# mainBoardV1.net
KiCad netlist of a schematic drawn in EAGLE
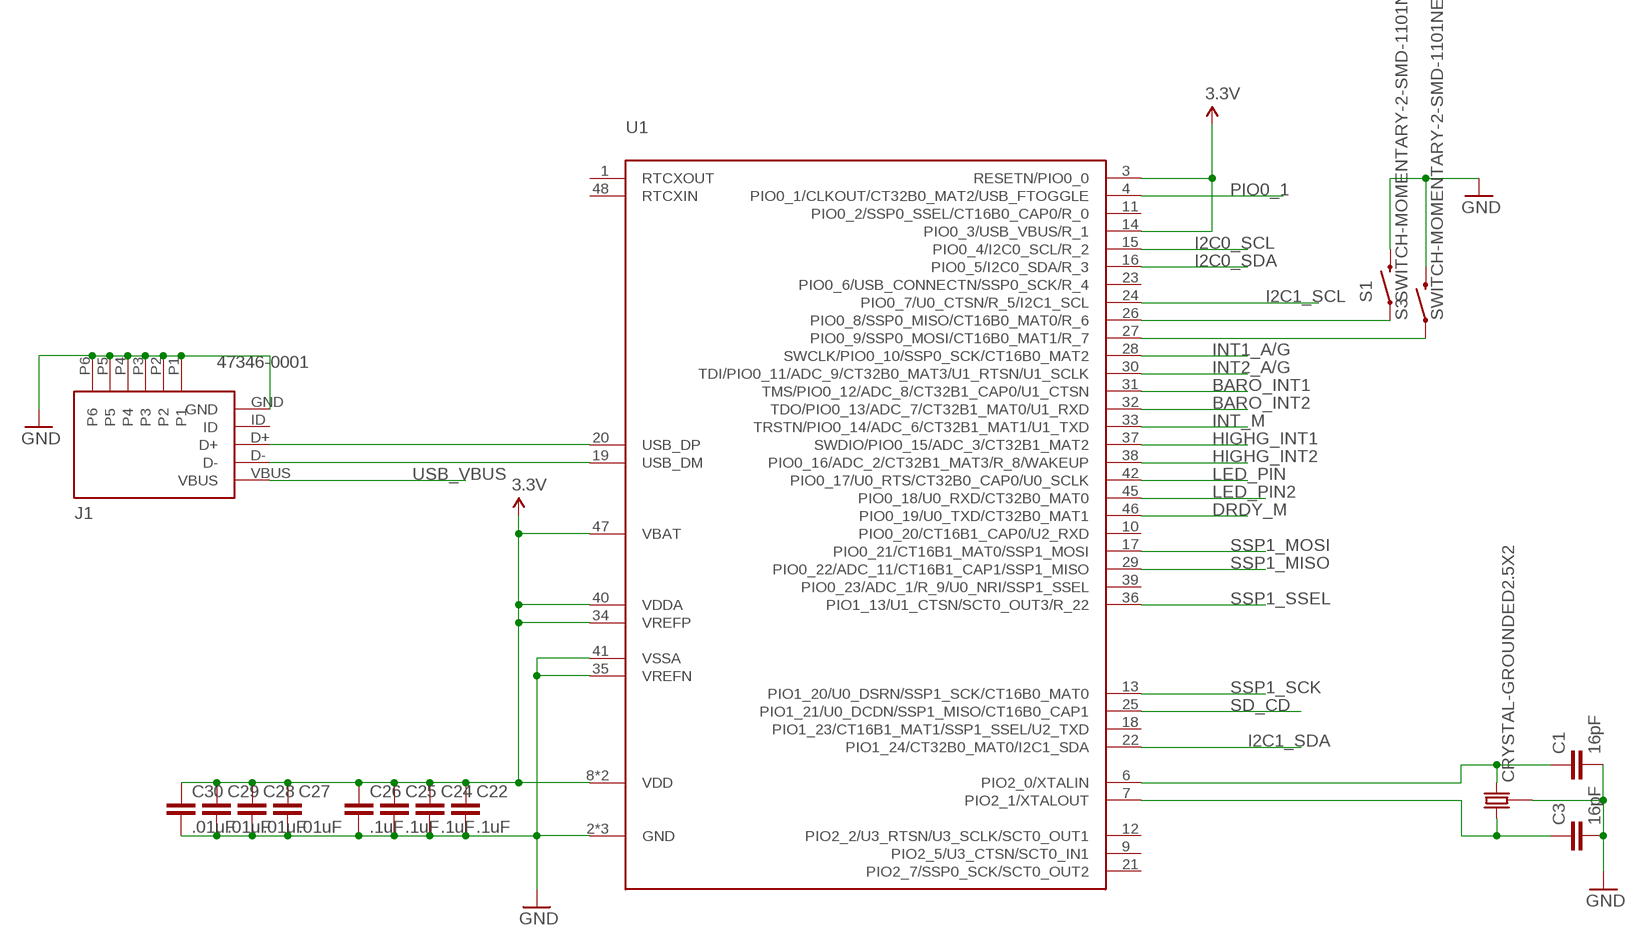
[diagram p0: schematic, sheet 1]
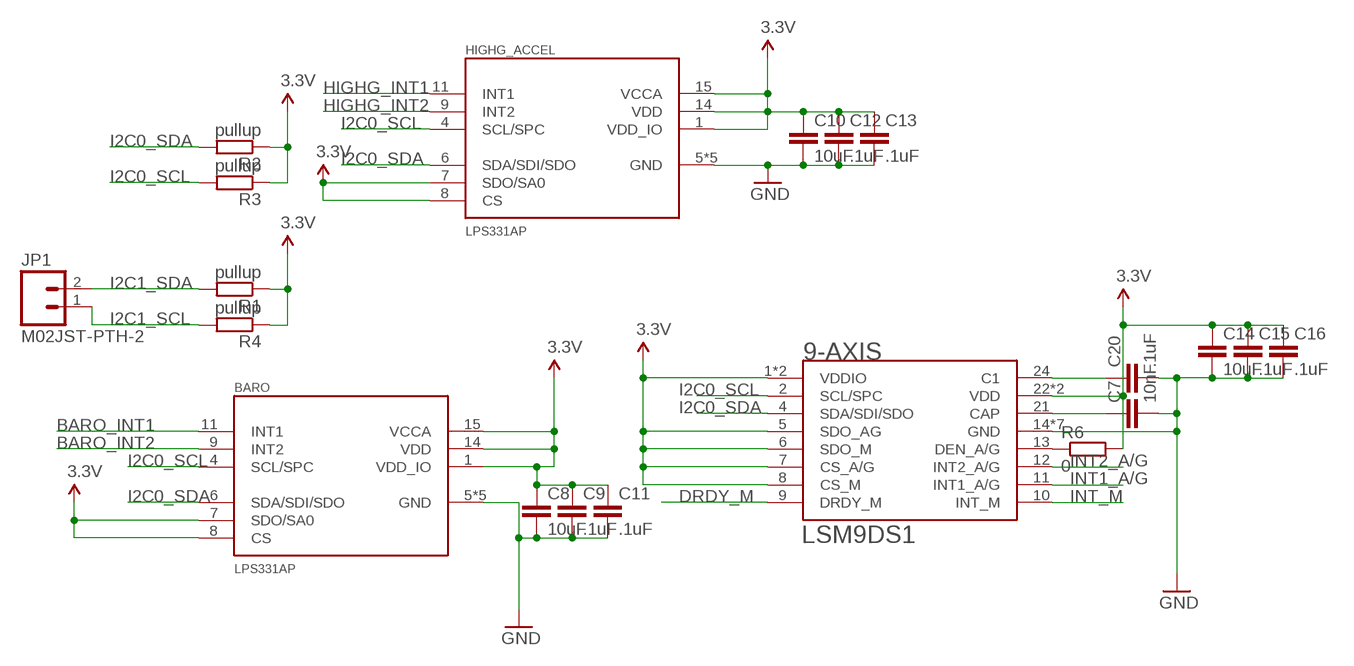
[diagram p1: schematic, sheet 2]
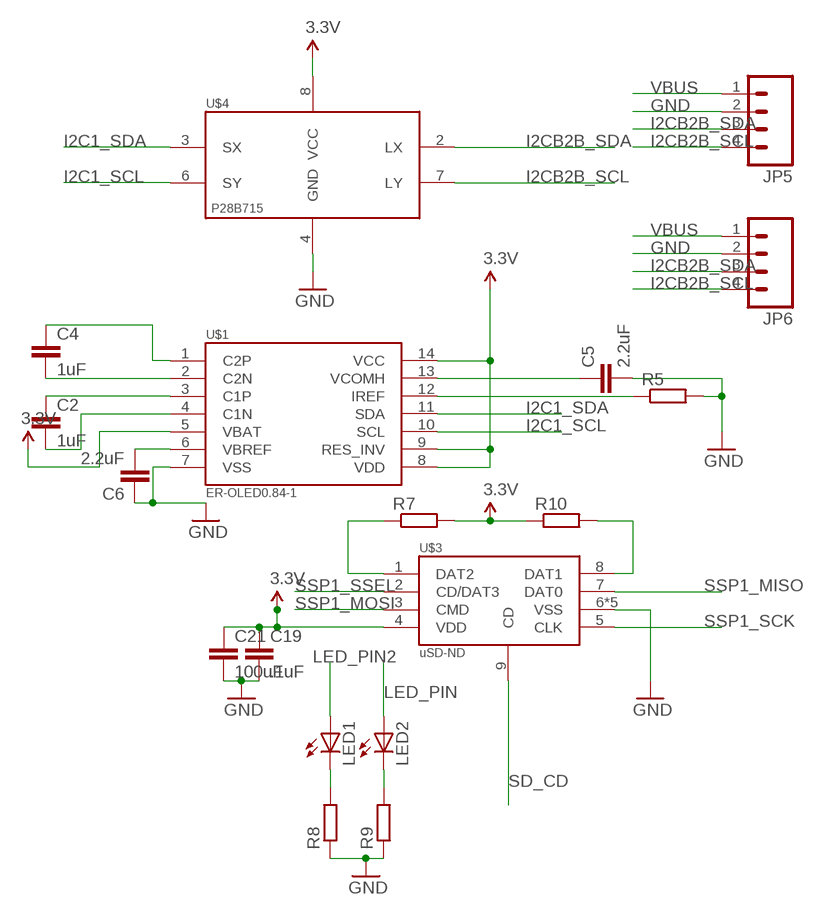
[diagram p2: schematic, sheet 3]
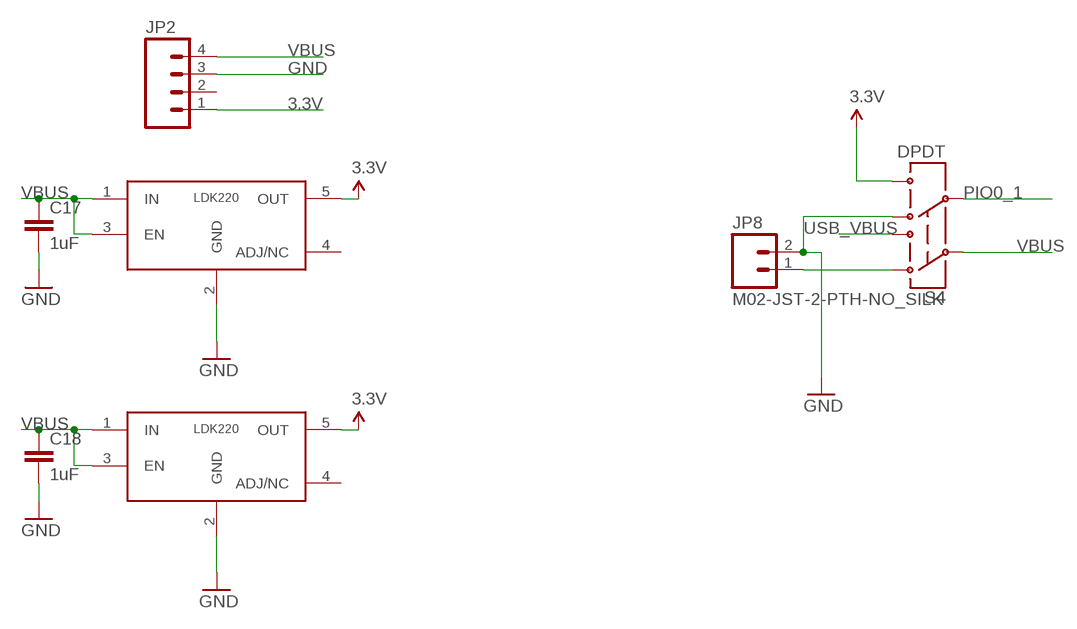
[diagram p3: schematic, sheet 4]

(export (version "E")
  (design (tool "Eeschema 10.0.6"))
  (components
    (comp (ref "C2")
      (value "1uF")
      (footprint "eagle-import:C0402")
      (fields (field (name "MPN") "MC0402X105M6R3CT"))
      (libsource (lib "eagle-import") (part "C0402"))
    )
    (comp (ref "C4")
      (value "1uF")
      (footprint "eagle-import:C0402")
      (fields (field (name "MPN") "MC0402X105M6R3CT"))
      (libsource (lib "eagle-import") (part "C0402"))
    )
    (comp (ref "C5")
      (value "2.2uF")
      (footprint "eagle-import:C0402")
      (fields (field (name "MPN") "C1005X6S0G225M050BC"))
      (libsource (lib "eagle-import") (part "C0402"))
    )
    (comp (ref "C6")
      (value "2.2uF")
      (footprint "eagle-import:C0402")
      (fields (field (name "MPN") "C1005X6S0G225M050BC"))
      (libsource (lib "eagle-import") (part "C0402"))
    )
    (comp (ref "C19")
      (value ".1uF")
      (footprint "eagle-import:C0402")
      (libsource (lib "eagle-import") (part "C0402"))
    )
    (comp (ref "C21")
      (value "100uF")
      (footprint "eagle-import:C1206")
      (libsource (lib "eagle-import") (part "CC1206"))
    )
    (comp (ref "JP5")
      (value "M04JST")
      (footprint "eagle-import:1X04-1.5MM_JST")
      (libsource (lib "eagle-import") (part "M04JST"))
    )
    (comp (ref "JP6")
      (value "M04JST")
      (footprint "eagle-import:1X04-1.5MM_JST")
      (libsource (lib "eagle-import") (part "M04JST"))
    )
    (comp (ref "LED1")
      (value "LEDCHIPLED_0603")
      (footprint "eagle-import:CHIPLED_0603")
      (libsource (lib "eagle-import") (part "LEDCHIPLED_0603"))
    )
    (comp (ref "LED2")
      (value "LEDCHIPLED_0603")
      (footprint "eagle-import:CHIPLED_0603")
      (libsource (lib "eagle-import") (part "LEDCHIPLED_0603"))
    )
    (comp (ref "R5")
      (value "R0402")
      (footprint "eagle-import:R0402")
      (libsource (lib "eagle-import") (part "R0402"))
    )
    (comp (ref "R7")
      (value "R0402")
      (footprint "eagle-import:R0402")
      (libsource (lib "eagle-import") (part "R0402"))
    )
    (comp (ref "R8")
      (value "R0402")
      (footprint "eagle-import:R0402")
      (libsource (lib "eagle-import") (part "R0402"))
    )
    (comp (ref "R9")
      (value "R0402")
      (footprint "eagle-import:R0402")
      (libsource (lib "eagle-import") (part "R0402"))
    )
    (comp (ref "R10")
      (value "R0402")
      (footprint "eagle-import:R0402")
      (libsource (lib "eagle-import") (part "R0402"))
    )
    (comp (ref "U$1")
      (value "ER-OLED0.84-1")
      (footprint "eagle-import:MOLEX_52892-1433")
      (libsource (lib "eagle-import") (part "ER-OLED0.84-1"))
    )
    (comp (ref "U$3")
      (value "MICROSD-CD")
      (footprint "eagle-import:MOLEX_SD-47352-101")
      (libsource (lib "eagle-import") (part "MICROSD-CD"))
    )
    (comp (ref "U$4")
      (value "P82B715")
      (footprint "eagle-import:SO8")
      (libsource (lib "eagle-import") (part "P82B715"))
    )
    (comp (ref "C1")
      (value "16pF")
      (footprint "eagle-import:C0402")
      (libsource (lib "eagle-import") (part "C0402"))
    )
    (comp (ref "C3")
      (value "16pF")
      (footprint "eagle-import:C0402")
      (libsource (lib "eagle-import") (part "C0402"))
    )
    (comp (ref "C22")
      (value ".1uF")
      (footprint "eagle-import:C0402")
      (libsource (lib "eagle-import") (part "C0402"))
    )
    (comp (ref "C24")
      (value ".1uF")
      (footprint "eagle-import:C0402")
      (libsource (lib "eagle-import") (part "C0402"))
    )
    (comp (ref "C25")
      (value ".1uF")
      (footprint "eagle-import:C0402")
      (libsource (lib "eagle-import") (part "C0402"))
    )
    (comp (ref "C26")
      (value ".1uF")
      (footprint "eagle-import:C0402")
      (libsource (lib "eagle-import") (part "C0402"))
    )
    (comp (ref "C27")
      (value ".01uF")
      (footprint "eagle-import:C0402")
      (libsource (lib "eagle-import") (part "C0402"))
    )
    (comp (ref "C28")
      (value ".01uF")
      (footprint "eagle-import:C0402")
      (libsource (lib "eagle-import") (part "C0402"))
    )
    (comp (ref "C29")
      (value ".01uF")
      (footprint "eagle-import:C0402")
      (libsource (lib "eagle-import") (part "C0402"))
    )
    (comp (ref "C30")
      (value ".01uF")
      (footprint "eagle-import:C0402")
      (libsource (lib "eagle-import") (part "C0402"))
    )
    (comp (ref "J1")
      (value "47346-0001")
      (footprint "eagle-import:MICRO_USB")
      (fields (field (name "PARTNO") "AS-ITM-00021"))
      (libsource (lib "eagle-import") (part "MICRO-USB"))
    )
    (comp (ref "S1")
      (value "SWITCH-MOMENTARY-2-SMD-1101NE")
      (footprint "eagle-import:TACTILE-SWITCH-1101NE")
      (libsource (lib "eagle-import") (part "SWITCH-MOMENTARY-2-SMD-1101NE"))
    )
    (comp (ref "S3")
      (value "SWITCH-MOMENTARY-2-SMD-1101NE")
      (footprint "eagle-import:TACTILE-SWITCH-1101NE")
      (libsource (lib "eagle-import") (part "SWITCH-MOMENTARY-2-SMD-1101NE"))
    )
    (comp (ref "U$5")
      (value "CRYSTAL-GROUNDED2.5X2")
      (footprint "eagle-import:CRYSTAL-SMD-2.5X2")
      (libsource (lib "eagle-import") (part "CRYSTAL-GROUNDED2.5X2"))
    )
    (comp (ref "U1")
      (value "LPC11U68JBD48")
      (footprint "eagle-import:LQFP48")
      (libsource (lib "eagle-import") (part "LPC11U68JBD48"))
    )
    (comp (ref "9-AXIS")
      (value "LSM9DS1")
      (footprint "eagle-import:LGA-24L-3.5X3X1")
      (libsource (lib "eagle-import") (part "LSM9DS1"))
    )
    (comp (ref "BARO")
      (value "LPS331AP")
      (footprint "eagle-import:LGA-16-3X3X1")
      (fields (field (name "MPN") "LPS331APTR"))
      (libsource (lib "eagle-import") (part "LPS331AP"))
    )
    (comp (ref "C7")
      (value "10nF")
      (footprint "eagle-import:C0402")
      (fields (field (name "MPN") "S103M47Z5UN63L0R"))
      (libsource (lib "eagle-import") (part "C0402"))
    )
    (comp (ref "C8")
      (value "10uF")
      (footprint "eagle-import:C0402")
      (libsource (lib "eagle-import") (part "C0402"))
    )
    (comp (ref "C9")
      (value ".1uF")
      (footprint "eagle-import:C0402")
      (libsource (lib "eagle-import") (part "C0402"))
    )
    (comp (ref "C10")
      (value "10uF")
      (footprint "eagle-import:C0402")
      (libsource (lib "eagle-import") (part "C0402"))
    )
    (comp (ref "C11")
      (value ".1uF")
      (footprint "eagle-import:C0402")
      (libsource (lib "eagle-import") (part "C0402"))
    )
    (comp (ref "C12")
      (value ".1uF")
      (footprint "eagle-import:C0402")
      (libsource (lib "eagle-import") (part "C0402"))
    )
    (comp (ref "C13")
      (value ".1uF")
      (footprint "eagle-import:C0402")
      (libsource (lib "eagle-import") (part "C0402"))
    )
    (comp (ref "C14")
      (value "10uF")
      (footprint "eagle-import:C0402")
      (libsource (lib "eagle-import") (part "C0402"))
    )
    (comp (ref "C15")
      (value ".1uF")
      (footprint "eagle-import:C0402")
      (libsource (lib "eagle-import") (part "C0402"))
    )
    (comp (ref "C16")
      (value ".1uF")
      (footprint "eagle-import:C0402")
      (libsource (lib "eagle-import") (part "C0402"))
    )
    (comp (ref "C20")
      (value ".1uF")
      (footprint "eagle-import:C0402")
      (fields (field (name "MPN") "S103M47Z5UN63L0R"))
      (libsource (lib "eagle-import") (part "C0402"))
    )
    (comp (ref "HIGHG_ACCEL")
      (value "LPS331AP")
      (footprint "eagle-import:LGA-16-3X3X1")
      (fields (field (name "MPN") "LPS331APTR"))
      (libsource (lib "eagle-import") (part "LPS331AP"))
    )
    (comp (ref "JP1")
      (value "M02JST-PTH-2")
      (footprint "eagle-import:JST-2-PTH")
      (libsource (lib "eagle-import") (part "M02JST-PTH-2"))
    )
    (comp (ref "R1")
      (value "pullup")
      (footprint "eagle-import:R0805")
      (libsource (lib "eagle-import") (part "R0805"))
    )
    (comp (ref "R2")
      (value "pullup")
      (footprint "eagle-import:R0402")
      (libsource (lib "eagle-import") (part "R0402"))
    )
    (comp (ref "R3")
      (value "pullup")
      (footprint "eagle-import:R0402")
      (libsource (lib "eagle-import") (part "R0402"))
    )
    (comp (ref "R4")
      (value "pullup")
      (footprint "eagle-import:R0805")
      (libsource (lib "eagle-import") (part "R0805"))
    )
    (comp (ref "R6")
      (value "0")
      (footprint "eagle-import:R0402")
      (libsource (lib "eagle-import") (part "R0402"))
    )
    (comp (ref "C17")
      (value "1uF")
      (footprint "eagle-import:C0402")
      (libsource (lib "eagle-import") (part "C0402"))
    )
    (comp (ref "C18")
      (value "1uF")
      (footprint "eagle-import:C0402")
      (libsource (lib "eagle-import") (part "C0402"))
    )
    (comp (ref "JP2")
      (value "M04JST")
      (footprint "eagle-import:1X04-1.5MM_JST")
      (libsource (lib "eagle-import") (part "M04JST"))
    )
    (comp (ref "JP8")
      (value "M02-JST-2-PTH-NO_SILK")
      (footprint "eagle-import:JST-2-PTH-NS")
      (libsource (lib "eagle-import") (part "M02-JST-2-PTH-NO_SILK"))
    )
    (comp (ref "S4")
      (value "DPDT")
      (footprint "eagle-import:AYZ0202")
      (libsource (lib "eagle-import") (part "SWITCH-DPDTAYZ0202"))
    )
    (comp (ref "U$2")
      (value "LDK220M33R")
      (footprint "eagle-import:SOT23-5")
      (libsource (lib "eagle-import") (part "LDK220M33R"))
    )
    (comp (ref "U$6")
      (value "LDK220M33R")
      (footprint "eagle-import:SOT23-5")
      (libsource (lib "eagle-import") (part "LDK220M33R"))
    )
  )
  (nets
    (net (code "1") (name "3.3V") (class "Default")
      (node (ref "9-AXIS") (pin "1") (pinfunction "VDDIO_1") (pintype "bidirectional"))
      (node (ref "9-AXIS") (pin "22") (pinfunction "VDD_22") (pintype "bidirectional"))
      (node (ref "9-AXIS") (pin "23") (pinfunction "VDD_23") (pintype "bidirectional"))
      (node (ref "9-AXIS") (pin "3") (pinfunction "VDDIO_3") (pintype "bidirectional"))
      (node (ref "9-AXIS") (pin "5") (pinfunction "SDO_AG_5") (pintype "bidirectional"))
      (node (ref "9-AXIS") (pin "6") (pinfunction "SDO_M_6") (pintype "bidirectional"))
      (node (ref "9-AXIS") (pin "7") (pinfunction "CS_A/G_7") (pintype "bidirectional"))
      (node (ref "9-AXIS") (pin "8") (pinfunction "CS_M_8") (pintype "bidirectional"))
      (node (ref "BARO") (pin "1") (pinfunction "VDD_IO_1") (pintype "bidirectional"))
      (node (ref "BARO") (pin "14") (pinfunction "VDD_14") (pintype "bidirectional"))
      (node (ref "BARO") (pin "15") (pinfunction "VCCA_15") (pintype "bidirectional"))
      (node (ref "BARO") (pin "7") (pinfunction "SDO/SA0_7") (pintype "bidirectional"))
      (node (ref "BARO") (pin "8") (pinfunction "CS_8") (pintype "bidirectional"))
      (node (ref "C10") (pin "1") (pinfunction "1_1") (pintype "passive"))
      (node (ref "C11") (pin "1") (pinfunction "1_1") (pintype "passive"))
      (node (ref "C12") (pin "1") (pinfunction "1_1") (pintype "passive"))
      (node (ref "C13") (pin "1") (pinfunction "1_1") (pintype "passive"))
      (node (ref "C14") (pin "1") (pinfunction "1_1") (pintype "passive"))
      (node (ref "C15") (pin "1") (pinfunction "1_1") (pintype "passive"))
      (node (ref "C16") (pin "1") (pinfunction "1_1") (pintype "passive"))
      (node (ref "C19") (pin "1") (pinfunction "1_1") (pintype "passive"))
      (node (ref "C21") (pin "1") (pinfunction "1_1") (pintype "passive"))
      (node (ref "C22") (pin "1") (pinfunction "1_1") (pintype "passive"))
      (node (ref "C24") (pin "1") (pinfunction "1_1") (pintype "passive"))
      (node (ref "C25") (pin "1") (pinfunction "1_1") (pintype "passive"))
      (node (ref "C26") (pin "1") (pinfunction "1_1") (pintype "passive"))
      (node (ref "C27") (pin "1") (pinfunction "1_1") (pintype "passive"))
      (node (ref "C28") (pin "1") (pinfunction "1_1") (pintype "passive"))
      (node (ref "C29") (pin "1") (pinfunction "1_1") (pintype "passive"))
      (node (ref "C30") (pin "1") (pinfunction "1_1") (pintype "passive"))
      (node (ref "C8") (pin "1") (pinfunction "1_1") (pintype "passive"))
      (node (ref "C9") (pin "1") (pinfunction "1_1") (pintype "passive"))
      (node (ref "HIGHG_ACCEL") (pin "1") (pinfunction "VDD_IO_1") (pintype "bidirectional"))
      (node (ref "HIGHG_ACCEL") (pin "14") (pinfunction "VDD_14") (pintype "bidirectional"))
      (node (ref "HIGHG_ACCEL") (pin "15") (pinfunction "VCCA_15") (pintype "bidirectional"))
      (node (ref "HIGHG_ACCEL") (pin "7") (pinfunction "SDO/SA0_7") (pintype "bidirectional"))
      (node (ref "HIGHG_ACCEL") (pin "8") (pinfunction "CS_8") (pintype "bidirectional"))
      (node (ref "JP2") (pin "1") (pinfunction "1_1") (pintype "passive"))
      (node (ref "R1") (pin "1") (pinfunction "1_1") (pintype "passive"))
      (node (ref "R10") (pin "1") (pinfunction "1_1") (pintype "passive"))
      (node (ref "R2") (pin "1") (pinfunction "1_1") (pintype "passive"))
      (node (ref "R3") (pin "1") (pinfunction "1_1") (pintype "passive"))
      (node (ref "R4") (pin "1") (pinfunction "1_1") (pintype "passive"))
      (node (ref "R6") (pin "2") (pinfunction "2_2") (pintype "passive"))
      (node (ref "R7") (pin "2") (pinfunction "2_2") (pintype "passive"))
      (node (ref "S4") (pin "6") (pinfunction "6_6") (pintype "bidirectional"))
      (node (ref "U$1") (pin "14") (pinfunction "VCC_14") (pintype "bidirectional"))
      (node (ref "U$1") (pin "5") (pinfunction "VBAT_5") (pintype "bidirectional"))
      (node (ref "U$1") (pin "8") (pinfunction "VDD_8") (pintype "bidirectional"))
      (node (ref "U$1") (pin "9") (pinfunction "RES_INV_9") (pintype "bidirectional"))
      (node (ref "U$2") (pin "5") (pinfunction "OUT_5") (pintype "bidirectional"))
      (node (ref "U$3") (pin "4") (pinfunction "VDD_4") (pintype "bidirectional"))
      (node (ref "U$4") (pin "8") (pinfunction "VCC_8") (pintype "bidirectional"))
      (node (ref "U$6") (pin "5") (pinfunction "OUT_5") (pintype "bidirectional"))
      (node (ref "U1") (pin "14") (pinfunction "PIO0_3/USB_VBUS/R_1_14") (pintype "bidirectional"))
      (node (ref "U1") (pin "3") (pinfunction "RESETN/PIO0_0_3") (pintype "bidirectional"))
      (node (ref "U1") (pin "34") (pinfunction "VREFP_34") (pintype "bidirectional"))
      (node (ref "U1") (pin "40") (pinfunction "VDDA_40") (pintype "bidirectional"))
      (node (ref "U1") (pin "44") (pinfunction "VDD_44") (pintype "bidirectional"))
      (node (ref "U1") (pin "47") (pinfunction "VBAT_47") (pintype "bidirectional"))
      (node (ref "U1") (pin "8") (pinfunction "VDD_8") (pintype "bidirectional"))
    )
    (net (code "2") (name "BARO_INT1") (class "Default")
      (node (ref "BARO") (pin "11") (pinfunction "INT1_11") (pintype "bidirectional"))
      (node (ref "U1") (pin "31") (pinfunction "TMS/PIO0_12/ADC_8/CT32B1_CAP0/U1_CTSN_31") (pintype "bidirectional"))
    )
    (net (code "3") (name "BARO_INT2") (class "Default")
      (node (ref "BARO") (pin "9") (pinfunction "INT2_9") (pintype "bidirectional"))
      (node (ref "U1") (pin "32") (pinfunction "TDO/PIO0_13/ADC_7/CT32B1_MAT0/U1_RXD_32") (pintype "bidirectional"))
    )
    (net (code "4") (name "DRDY_M") (class "Default")
      (node (ref "9-AXIS") (pin "9") (pinfunction "DRDY_M_9") (pintype "bidirectional"))
      (node (ref "U1") (pin "46") (pinfunction "PIO0_19/U0_TXD/CT32B0_MAT1_46") (pintype "bidirectional"))
    )
    (net (code "5") (name "GND") (class "Default")
      (node (ref "9-AXIS") (pin "14") (pinfunction "GND_14") (pintype "bidirectional"))
      (node (ref "9-AXIS") (pin "15") (pinfunction "GND_15") (pintype "bidirectional"))
      (node (ref "9-AXIS") (pin "16") (pinfunction "GND_16") (pintype "bidirectional"))
      (node (ref "9-AXIS") (pin "17") (pinfunction "GND_17") (pintype "bidirectional"))
      (node (ref "9-AXIS") (pin "18") (pinfunction "GND_18") (pintype "bidirectional"))
      (node (ref "9-AXIS") (pin "19") (pinfunction "GND_19") (pintype "bidirectional"))
      (node (ref "9-AXIS") (pin "20") (pinfunction "GND_20") (pintype "bidirectional"))
      (node (ref "BARO") (pin "10") (pinfunction "GND_10") (pintype "bidirectional"))
      (node (ref "BARO") (pin "12") (pinfunction "GND_12") (pintype "bidirectional"))
      (node (ref "BARO") (pin "13") (pinfunction "GND_13") (pintype "bidirectional"))
      (node (ref "BARO") (pin "16") (pinfunction "GND_16") (pintype "bidirectional"))
      (node (ref "BARO") (pin "5") (pinfunction "GND_5") (pintype "bidirectional"))
      (node (ref "C1") (pin "2") (pinfunction "2_2") (pintype "passive"))
      (node (ref "C10") (pin "2") (pinfunction "2_2") (pintype "passive"))
      (node (ref "C11") (pin "2") (pinfunction "2_2") (pintype "passive"))
      (node (ref "C12") (pin "2") (pinfunction "2_2") (pintype "passive"))
      (node (ref "C13") (pin "2") (pinfunction "2_2") (pintype "passive"))
      (node (ref "C14") (pin "2") (pinfunction "2_2") (pintype "passive"))
      (node (ref "C15") (pin "2") (pinfunction "2_2") (pintype "passive"))
      (node (ref "C16") (pin "2") (pinfunction "2_2") (pintype "passive"))
      (node (ref "C17") (pin "2") (pinfunction "2_2") (pintype "passive"))
      (node (ref "C18") (pin "2") (pinfunction "2_2") (pintype "passive"))
      (node (ref "C19") (pin "2") (pinfunction "2_2") (pintype "passive"))
      (node (ref "C20") (pin "2") (pinfunction "2_2") (pintype "passive"))
      (node (ref "C21") (pin "2") (pinfunction "2_2") (pintype "passive"))
      (node (ref "C22") (pin "2") (pinfunction "2_2") (pintype "passive"))
      (node (ref "C24") (pin "2") (pinfunction "2_2") (pintype "passive"))
      (node (ref "C25") (pin "2") (pinfunction "2_2") (pintype "passive"))
      (node (ref "C26") (pin "2") (pinfunction "2_2") (pintype "passive"))
      (node (ref "C27") (pin "2") (pinfunction "2_2") (pintype "passive"))
      (node (ref "C28") (pin "2") (pinfunction "2_2") (pintype "passive"))
      (node (ref "C29") (pin "2") (pinfunction "2_2") (pintype "passive"))
      (node (ref "C3") (pin "2") (pinfunction "2_2") (pintype "passive"))
      (node (ref "C30") (pin "2") (pinfunction "2_2") (pintype "passive"))
      (node (ref "C5") (pin "2") (pinfunction "2_2") (pintype "passive"))
      (node (ref "C6") (pin "1") (pinfunction "1_1") (pintype "passive"))
      (node (ref "C7") (pin "2") (pinfunction "2_2") (pintype "passive"))
      (node (ref "C8") (pin "2") (pinfunction "2_2") (pintype "passive"))
      (node (ref "C9") (pin "2") (pinfunction "2_2") (pintype "passive"))
      (node (ref "HIGHG_ACCEL") (pin "10") (pinfunction "GND_10") (pintype "bidirectional"))
      (node (ref "HIGHG_ACCEL") (pin "12") (pinfunction "GND_12") (pintype "bidirectional"))
      (node (ref "HIGHG_ACCEL") (pin "13") (pinfunction "GND_13") (pintype "bidirectional"))
      (node (ref "HIGHG_ACCEL") (pin "16") (pinfunction "GND_16") (pintype "bidirectional"))
      (node (ref "HIGHG_ACCEL") (pin "5") (pinfunction "GND_5") (pintype "bidirectional"))
      (node (ref "J1") (pin "GND") (pinfunction "GND_GND") (pintype "bidirectional"))
      (node (ref "J1") (pin "P1") (pinfunction "P1_P1") (pintype "bidirectional"))
      (node (ref "J1") (pin "P2") (pinfunction "P2_P2") (pintype "bidirectional"))
      (node (ref "J1") (pin "P3") (pinfunction "P3_P3") (pintype "bidirectional"))
      (node (ref "J1") (pin "P4") (pinfunction "P4_P4") (pintype "bidirectional"))
      (node (ref "J1") (pin "P5") (pinfunction "P5_P5") (pintype "bidirectional"))
      (node (ref "J1") (pin "P6") (pinfunction "P6_P6") (pintype "bidirectional"))
      (node (ref "JP2") (pin "3") (pinfunction "3_3") (pintype "passive"))
      (node (ref "JP5") (pin "2") (pinfunction "2_2") (pintype "passive"))
      (node (ref "JP6") (pin "2") (pinfunction "2_2") (pintype "passive"))
      (node (ref "JP8") (pin "2") (pinfunction "2_2") (pintype "passive"))
      (node (ref "R5") (pin "2") (pinfunction "2_2") (pintype "passive"))
      (node (ref "R8") (pin "1") (pinfunction "1_1") (pintype "passive"))
      (node (ref "R9") (pin "1") (pinfunction "1_1") (pintype "passive"))
      (node (ref "S1") (pin "2") (pinfunction "2_2") (pintype "passive"))
      (node (ref "S3") (pin "2") (pinfunction "2_2") (pintype "passive"))
      (node (ref "S4") (pin "4") (pinfunction "4_4") (pintype "bidirectional"))
      (node (ref "U$1") (pin "7") (pinfunction "VSS_7") (pintype "bidirectional"))
      (node (ref "U$2") (pin "2") (pinfunction "GND_2") (pintype "bidirectional"))
      (node (ref "U$3") (pin "6") (pinfunction "VSS_6") (pintype "bidirectional"))
      (node (ref "U$3") (pin "G1") (pinfunction "VSS_G1") (pintype "bidirectional"))
      (node (ref "U$3") (pin "G2") (pinfunction "VSS_G2") (pintype "bidirectional"))
      (node (ref "U$3") (pin "G3") (pinfunction "VSS_G3") (pintype "bidirectional"))
      (node (ref "U$3") (pin "G4") (pinfunction "VSS_G4") (pintype "bidirectional"))
      (node (ref "U$4") (pin "4") (pinfunction "GND_4") (pintype "bidirectional"))
      (node (ref "U$5") (pin "GND1") (pinfunction "3_GND1") (pintype "passive"))
      (node (ref "U$5") (pin "GND2") (pinfunction "3_GND2") (pintype "passive"))
      (node (ref "U$6") (pin "2") (pinfunction "GND_2") (pintype "bidirectional"))
      (node (ref "U1") (pin "2") (pinfunction "GND_2") (pintype "bidirectional"))
      (node (ref "U1") (pin "35") (pinfunction "VREFN_35") (pintype "bidirectional"))
      (node (ref "U1") (pin "41") (pinfunction "VSSA_41") (pintype "bidirectional"))
      (node (ref "U1") (pin "43") (pinfunction "GND_43") (pintype "bidirectional"))
      (node (ref "U1") (pin "5") (pinfunction "GND_5") (pintype "bidirectional"))
    )
    (net (code "6") (name "HIGHG_INT1") (class "Default")
      (node (ref "HIGHG_ACCEL") (pin "11") (pinfunction "INT1_11") (pintype "bidirectional"))
      (node (ref "U1") (pin "37") (pinfunction "SWDIO/PIO0_15/ADC_3/CT32B1_MAT2_37") (pintype "bidirectional"))
    )
    (net (code "7") (name "HIGHG_INT2") (class "Default")
      (node (ref "HIGHG_ACCEL") (pin "9") (pinfunction "INT2_9") (pintype "bidirectional"))
      (node (ref "U1") (pin "38") (pinfunction "PIO0_16/ADC_2/CT32B1_MAT3/R_8/WAKEUP_38") (pintype "bidirectional"))
    )
    (net (code "8") (name "I2C0_SCL") (class "Default")
      (node (ref "9-AXIS") (pin "2") (pinfunction "SCL/SPC_2") (pintype "bidirectional"))
      (node (ref "BARO") (pin "4") (pinfunction "SCL/SPC_4") (pintype "bidirectional"))
      (node (ref "HIGHG_ACCEL") (pin "4") (pinfunction "SCL/SPC_4") (pintype "bidirectional"))
      (node (ref "R3") (pin "2") (pinfunction "2_2") (pintype "passive"))
      (node (ref "U1") (pin "15") (pinfunction "PIO0_4/I2C0_SCL/R_2_15") (pintype "bidirectional"))
    )
    (net (code "9") (name "I2C0_SDA") (class "Default")
      (node (ref "9-AXIS") (pin "4") (pinfunction "SDA/SDI/SDO_4") (pintype "bidirectional"))
      (node (ref "BARO") (pin "6") (pinfunction "SDA/SDI/SDO_6") (pintype "bidirectional"))
      (node (ref "HIGHG_ACCEL") (pin "6") (pinfunction "SDA/SDI/SDO_6") (pintype "bidirectional"))
      (node (ref "R2") (pin "2") (pinfunction "2_2") (pintype "passive"))
      (node (ref "U1") (pin "16") (pinfunction "PIO0_5/I2C0_SDA/R_3_16") (pintype "bidirectional"))
    )
    (net (code "10") (name "I2C1_SCL") (class "Default")
      (node (ref "JP1") (pin "1") (pinfunction "1_1") (pintype "passive"))
      (node (ref "R4") (pin "2") (pinfunction "2_2") (pintype "passive"))
      (node (ref "U$1") (pin "10") (pinfunction "SCL_10") (pintype "bidirectional"))
      (node (ref "U$4") (pin "6") (pinfunction "SY_6") (pintype "bidirectional"))
      (node (ref "U1") (pin "24") (pinfunction "PIO0_7/U0_CTSN/R_5/I2C1_SCL_24") (pintype "bidirectional"))
    )
    (net (code "11") (name "I2C1_SDA") (class "Default")
      (node (ref "JP1") (pin "2") (pinfunction "2_2") (pintype "passive"))
      (node (ref "R1") (pin "2") (pinfunction "2_2") (pintype "passive"))
      (node (ref "U$1") (pin "11") (pinfunction "SDA_11") (pintype "bidirectional"))
      (node (ref "U$4") (pin "3") (pinfunction "SX_3") (pintype "bidirectional"))
      (node (ref "U1") (pin "22") (pinfunction "PIO1_24/CT32B0_MAT0/I2C1_SDA_22") (pintype "bidirectional"))
    )
    (net (code "12") (name "I2CB2B_SCL") (class "Default")
      (node (ref "JP5") (pin "4") (pinfunction "4_4") (pintype "passive"))
      (node (ref "JP6") (pin "4") (pinfunction "4_4") (pintype "passive"))
      (node (ref "U$4") (pin "7") (pinfunction "LY_7") (pintype "bidirectional"))
    )
    (net (code "13") (name "I2CB2B_SDA") (class "Default")
      (node (ref "JP5") (pin "3") (pinfunction "3_3") (pintype "passive"))
      (node (ref "JP6") (pin "3") (pinfunction "3_3") (pintype "passive"))
      (node (ref "U$4") (pin "2") (pinfunction "LX_2") (pintype "bidirectional"))
    )
    (net (code "14") (name "INT1_A{slash}G") (class "Default")
      (node (ref "9-AXIS") (pin "11") (pinfunction "INT1_A/G_11") (pintype "bidirectional"))
      (node (ref "U1") (pin "28") (pinfunction "SWCLK/PIO0_10/SSP0_SCK/CT16B0_MAT2_28") (pintype "bidirectional"))
    )
    (net (code "15") (name "INT2_A{slash}G") (class "Default")
      (node (ref "9-AXIS") (pin "12") (pinfunction "INT2_A/G_12") (pintype "bidirectional"))
      (node (ref "U1") (pin "30") (pinfunction "TDI/PIO0_11/ADC_9/CT32B0_MAT3/U1_RTSN/U1_SCLK_30") (pintype "bidirectional"))
    )
    (net (code "16") (name "INT_M") (class "Default")
      (node (ref "9-AXIS") (pin "10") (pinfunction "INT_M_10") (pintype "bidirectional"))
      (node (ref "U1") (pin "33") (pinfunction "TRSTN/PIO0_14/ADC_6/CT32B1_MAT1/U1_TXD_33") (pintype "bidirectional"))
    )
    (net (code "17") (name "LED_PIN") (class "Default")
      (node (ref "LED2") (pin "A") (pinfunction "A_A") (pintype "passive"))
      (node (ref "U1") (pin "42") (pinfunction "PIO0_17/U0_RTS/CT32B0_CAP0/U0_SCLK_42") (pintype "bidirectional"))
    )
    (net (code "18") (name "LED_PIN2") (class "Default")
      (node (ref "LED1") (pin "A") (pinfunction "A_A") (pintype "passive"))
      (node (ref "U1") (pin "45") (pinfunction "PIO0_18/U0_RXD/CT32B0_MAT0_45") (pintype "bidirectional"))
    )
    (net (code "19") (name "Net-(9-AXIS-C1)") (class "Default")
      (node (ref "9-AXIS") (pin "24") (pinfunction "C1_24") (pintype "bidirectional"))
      (node (ref "C20") (pin "1") (pinfunction "1_1") (pintype "passive"))
    )
    (net (code "20") (name "Net-(9-AXIS-CAP)") (class "Default")
      (node (ref "9-AXIS") (pin "21") (pinfunction "CAP_21") (pintype "bidirectional"))
      (node (ref "C7") (pin "1") (pinfunction "1_1") (pintype "passive"))
    )
    (net (code "21") (name "Net-(9-AXIS-DEN_A{slash}G)") (class "Default")
      (node (ref "9-AXIS") (pin "13") (pinfunction "DEN_A/G_13") (pintype "bidirectional"))
      (node (ref "R6") (pin "1") (pinfunction "1_1") (pintype "passive"))
    )
    (net (code "22") (name "Net-(JP8-Pad1)") (class "Default")
      (node (ref "JP8") (pin "1") (pinfunction "1_1") (pintype "passive"))
      (node (ref "S4") (pin "1") (pinfunction "1_1") (pintype "bidirectional"))
    )
    (net (code "23") (name "Net-(LED1-PadC)") (class "Default")
      (node (ref "LED1") (pin "C") (pinfunction "C_C") (pintype "passive"))
      (node (ref "R8") (pin "2") (pinfunction "2_2") (pintype "passive"))
    )
    (net (code "24") (name "Net-(LED2-PadC)") (class "Default")
      (node (ref "LED2") (pin "C") (pinfunction "C_C") (pintype "passive"))
      (node (ref "R9") (pin "2") (pinfunction "2_2") (pintype "passive"))
    )
    (net (code "25") (name "Net-(U$1-C1N)") (class "Default")
      (node (ref "C2") (pin "2") (pinfunction "2_2") (pintype "passive"))
      (node (ref "U$1") (pin "4") (pinfunction "C1N_4") (pintype "bidirectional"))
    )
    (net (code "26") (name "Net-(U$1-C1P)") (class "Default")
      (node (ref "C2") (pin "1") (pinfunction "1_1") (pintype "passive"))
      (node (ref "U$1") (pin "3") (pinfunction "C1P_3") (pintype "bidirectional"))
    )
    (net (code "27") (name "Net-(U$1-C2N)") (class "Default")
      (node (ref "C4") (pin "2") (pinfunction "2_2") (pintype "passive"))
      (node (ref "U$1") (pin "2") (pinfunction "C2N_2") (pintype "bidirectional"))
    )
    (net (code "28") (name "Net-(U$1-C2P)") (class "Default")
      (node (ref "C4") (pin "1") (pinfunction "1_1") (pintype "passive"))
      (node (ref "U$1") (pin "1") (pinfunction "C2P_1") (pintype "bidirectional"))
    )
    (net (code "29") (name "Net-(U$1-IREF)") (class "Default")
      (node (ref "R5") (pin "1") (pinfunction "1_1") (pintype "passive"))
      (node (ref "U$1") (pin "12") (pinfunction "IREF_12") (pintype "bidirectional"))
    )
    (net (code "30") (name "Net-(U$1-VBREF)") (class "Default")
      (node (ref "C6") (pin "2") (pinfunction "2_2") (pintype "passive"))
      (node (ref "U$1") (pin "6") (pinfunction "VBREF_6") (pintype "bidirectional"))
    )
    (net (code "31") (name "Net-(U$1-VCOMH)") (class "Default")
      (node (ref "C5") (pin "1") (pinfunction "1_1") (pintype "passive"))
      (node (ref "U$1") (pin "13") (pinfunction "VCOMH_13") (pintype "bidirectional"))
    )
    (net (code "32") (name "Net-(U$3-DAT1)") (class "Default")
      (node (ref "R10") (pin "2") (pinfunction "2_2") (pintype "passive"))
      (node (ref "U$3") (pin "8") (pinfunction "DAT1_8") (pintype "bidirectional"))
    )
    (net (code "33") (name "Net-(U$3-DAT2)") (class "Default")
      (node (ref "R7") (pin "1") (pinfunction "1_1") (pintype "passive"))
      (node (ref "U$3") (pin "1") (pinfunction "DAT2_1") (pintype "bidirectional"))
    )
    (net (code "34") (name "Net-(U$5-1)") (class "Default")
      (node (ref "C3") (pin "1") (pinfunction "1_1") (pintype "passive"))
      (node (ref "U$5") (pin "P1") (pinfunction "1_P1") (pintype "passive"))
      (node (ref "U1") (pin "7") (pinfunction "PIO2_1/XTALOUT_7") (pintype "bidirectional"))
    )
    (net (code "35") (name "Net-(U$5-2)") (class "Default")
      (node (ref "C1") (pin "1") (pinfunction "1_1") (pintype "passive"))
      (node (ref "U$5") (pin "P2") (pinfunction "2_P2") (pintype "passive"))
      (node (ref "U1") (pin "6") (pinfunction "PIO2_0/XTALIN_6") (pintype "bidirectional"))
    )
    (net (code "36") (name "Net-(U1-PIO0_8{slash}SSP0_MISO{slash}CT16B0_MAT0{slash}R_6)") (class "Default")
      (node (ref "S1") (pin "1") (pinfunction "1_1") (pintype "passive"))
      (node (ref "U1") (pin "26") (pinfunction "PIO0_8/SSP0_MISO/CT16B0_MAT0/R_6_26") (pintype "bidirectional"))
    )
    (net (code "37") (name "Net-(U1-PIO0_9{slash}SSP0_MOSI{slash}CT16B0_MAT1{slash}R_7)") (class "Default")
      (node (ref "S3") (pin "1") (pinfunction "1_1") (pintype "passive"))
      (node (ref "U1") (pin "27") (pinfunction "PIO0_9/SSP0_MOSI/CT16B0_MAT1/R_7_27") (pintype "bidirectional"))
    )
    (net (code "38") (name "Net-(U1-USB_DM)") (class "Default")
      (node (ref "J1") (pin "D-") (pinfunction "D-_D-") (pintype "bidirectional"))
      (node (ref "U1") (pin "19") (pinfunction "USB_DM_19") (pintype "bidirectional"))
    )
    (net (code "39") (name "Net-(U1-USB_DP)") (class "Default")
      (node (ref "J1") (pin "D+") (pinfunction "D+_D+") (pintype "bidirectional"))
      (node (ref "U1") (pin "20") (pinfunction "USB_DP_20") (pintype "bidirectional"))
    )
    (net (code "40") (name "PIO0_1") (class "Default")
      (node (ref "S4") (pin "5") (pinfunction "5_5") (pintype "bidirectional"))
      (node (ref "U1") (pin "4") (pinfunction "PIO0_1/CLKOUT/CT32B0_MAT2/USB_FTOGGLE_4") (pintype "bidirectional"))
    )
    (net (code "41") (name "SD_CD") (class "Default")
      (node (ref "U$3") (pin "9") (pinfunction "CD_9") (pintype "bidirectional"))
      (node (ref "U1") (pin "25") (pinfunction "PIO1_21/U0_DCDN/SSP1_MISO/CT16B0_CAP1_25") (pintype "bidirectional"))
    )
    (net (code "42") (name "SSP1_MISO") (class "Default")
      (node (ref "U$3") (pin "7") (pinfunction "DAT0_7") (pintype "bidirectional"))
      (node (ref "U1") (pin "29") (pinfunction "PIO0_22/ADC_11/CT16B1_CAP1/SSP1_MISO_29") (pintype "bidirectional"))
    )
    (net (code "43") (name "SSP1_MOSI") (class "Default")
      (node (ref "U$3") (pin "3") (pinfunction "CMD_3") (pintype "bidirectional"))
      (node (ref "U1") (pin "17") (pinfunction "PIO0_21/CT16B1_MAT0/SSP1_MOSI_17") (pintype "bidirectional"))
    )
    (net (code "44") (name "SSP1_SCK") (class "Default")
      (node (ref "U$3") (pin "5") (pinfunction "CLK_5") (pintype "bidirectional"))
      (node (ref "U1") (pin "13") (pinfunction "PIO1_20/U0_DSRN/SSP1_SCK/CT16B0_MAT0_13") (pintype "bidirectional"))
    )
    (net (code "45") (name "SSP1_SSEL") (class "Default")
      (node (ref "U$3") (pin "2") (pinfunction "CD/DAT3_2") (pintype "bidirectional"))
      (node (ref "U1") (pin "36") (pinfunction "PIO1_13/U1_CTSN/SCT0_OUT3/R_22_36") (pintype "bidirectional"))
    )
    (net (code "46") (name "USB_VBUS") (class "Default")
      (node (ref "J1") (pin "VBUS") (pinfunction "VBUS_VBUS") (pintype "bidirectional"))
      (node (ref "S4") (pin "3") (pinfunction "3_3") (pintype "bidirectional"))
    )
    (net (code "47") (name "VBUS") (class "Default")
      (node (ref "C17") (pin "1") (pinfunction "1_1") (pintype "passive"))
      (node (ref "C18") (pin "1") (pinfunction "1_1") (pintype "passive"))
      (node (ref "JP2") (pin "4") (pinfunction "4_4") (pintype "passive"))
      (node (ref "JP5") (pin "1") (pinfunction "1_1") (pintype "passive"))
      (node (ref "JP6") (pin "1") (pinfunction "1_1") (pintype "passive"))
      (node (ref "S4") (pin "2") (pinfunction "2_2") (pintype "bidirectional"))
      (node (ref "U$2") (pin "1") (pinfunction "IN_1") (pintype "bidirectional"))
      (node (ref "U$2") (pin "3") (pinfunction "EN_3") (pintype "bidirectional"))
      (node (ref "U$6") (pin "1") (pinfunction "IN_1") (pintype "bidirectional"))
      (node (ref "U$6") (pin "3") (pinfunction "EN_3") (pintype "bidirectional"))
    )
    (net (code "48") (name "unconnected-(J1-PadID)") (class "Default")
      (node (ref "J1") (pin "ID") (pinfunction "ID_ID") (pintype "bidirectional"))
    )
    (net (code "49") (name "unconnected-(JP2-Pad2)") (class "Default")
      (node (ref "JP2") (pin "2") (pinfunction "2_2") (pintype "passive"))
    )
    (net (code "50") (name "unconnected-(U$2-ADJ{slash}NC-Pad4)") (class "Default")
      (node (ref "U$2") (pin "4") (pinfunction "ADJ/NC_4") (pintype "bidirectional"))
    )
    (net (code "51") (name "unconnected-(U$6-ADJ{slash}NC-Pad4)") (class "Default")
      (node (ref "U$6") (pin "4") (pinfunction "ADJ/NC_4") (pintype "bidirectional"))
    )
    (net (code "52") (name "unconnected-(U1-PIO0_2{slash}SSP0_SSEL{slash}CT16B0_CAP0{slash}R_0-Pad11)") (class "Default")
      (node (ref "U1") (pin "11") (pinfunction "PIO0_2/SSP0_SSEL/CT16B0_CAP0/R_0_11") (pintype "bidirectional"))
    )
    (net (code "53") (name "unconnected-(U1-PIO0_6{slash}USB_CONNECTN{slash}SSP0_SCK{slash}R_4-Pad23)") (class "Default")
      (node (ref "U1") (pin "23") (pinfunction "PIO0_6/USB_CONNECTN/SSP0_SCK/R_4_23") (pintype "bidirectional"))
    )
    (net (code "54") (name "unconnected-(U1-PIO0_20{slash}CT16B1_CAP0{slash}U2_RXD-Pad10)") (class "Default")
      (node (ref "U1") (pin "10") (pinfunction "PIO0_20/CT16B1_CAP0/U2_RXD_10") (pintype "bidirectional"))
    )
    (net (code "55") (name "unconnected-(U1-PIO0_23{slash}ADC_1{slash}R_9{slash}U0_NRI{slash}SSP1_SSEL-Pad39)") (class "Default")
      (node (ref "U1") (pin "39") (pinfunction "PIO0_23/ADC_1/R_9/U0_NRI/SSP1_SSEL_39") (pintype "bidirectional"))
    )
    (net (code "56") (name "unconnected-(U1-PIO1_23{slash}CT16B1_MAT1{slash}SSP1_SSEL{slash}U2_TXD-Pad18)") (class "Default")
      (node (ref "U1") (pin "18") (pinfunction "PIO1_23/CT16B1_MAT1/SSP1_SSEL/U2_TXD_18") (pintype "bidirectional"))
    )
    (net (code "57") (name "unconnected-(U1-PIO2_2{slash}U3_RTSN{slash}U3_SCLK{slash}SCT0_OUT1-Pad12)") (class "Default")
      (node (ref "U1") (pin "12") (pinfunction "PIO2_2/U3_RTSN/U3_SCLK/SCT0_OUT1_12") (pintype "bidirectional"))
    )
    (net (code "58") (name "unconnected-(U1-PIO2_5{slash}U3_CTSN{slash}SCT0_IN1-Pad9)") (class "Default")
      (node (ref "U1") (pin "9") (pinfunction "PIO2_5/U3_CTSN/SCT0_IN1_9") (pintype "bidirectional"))
    )
    (net (code "59") (name "unconnected-(U1-PIO2_7{slash}SSP0_SCK{slash}SCT0_OUT2-Pad21)") (class "Default")
      (node (ref "U1") (pin "21") (pinfunction "PIO2_7/SSP0_SCK/SCT0_OUT2_21") (pintype "bidirectional"))
    )
    (net (code "60") (name "unconnected-(U1-RTCXIN-Pad48)") (class "Default")
      (node (ref "U1") (pin "48") (pinfunction "RTCXIN_48") (pintype "bidirectional"))
    )
    (net (code "61") (name "unconnected-(U1-RTCXOUT-Pad1)") (class "Default")
      (node (ref "U1") (pin "1") (pinfunction "RTCXOUT_1") (pintype "bidirectional"))
    )
  )
)
